# dc26_maneki-neko_badge_page01_20180626.net
KiCad netlist of a schematic drawn in EAGLE
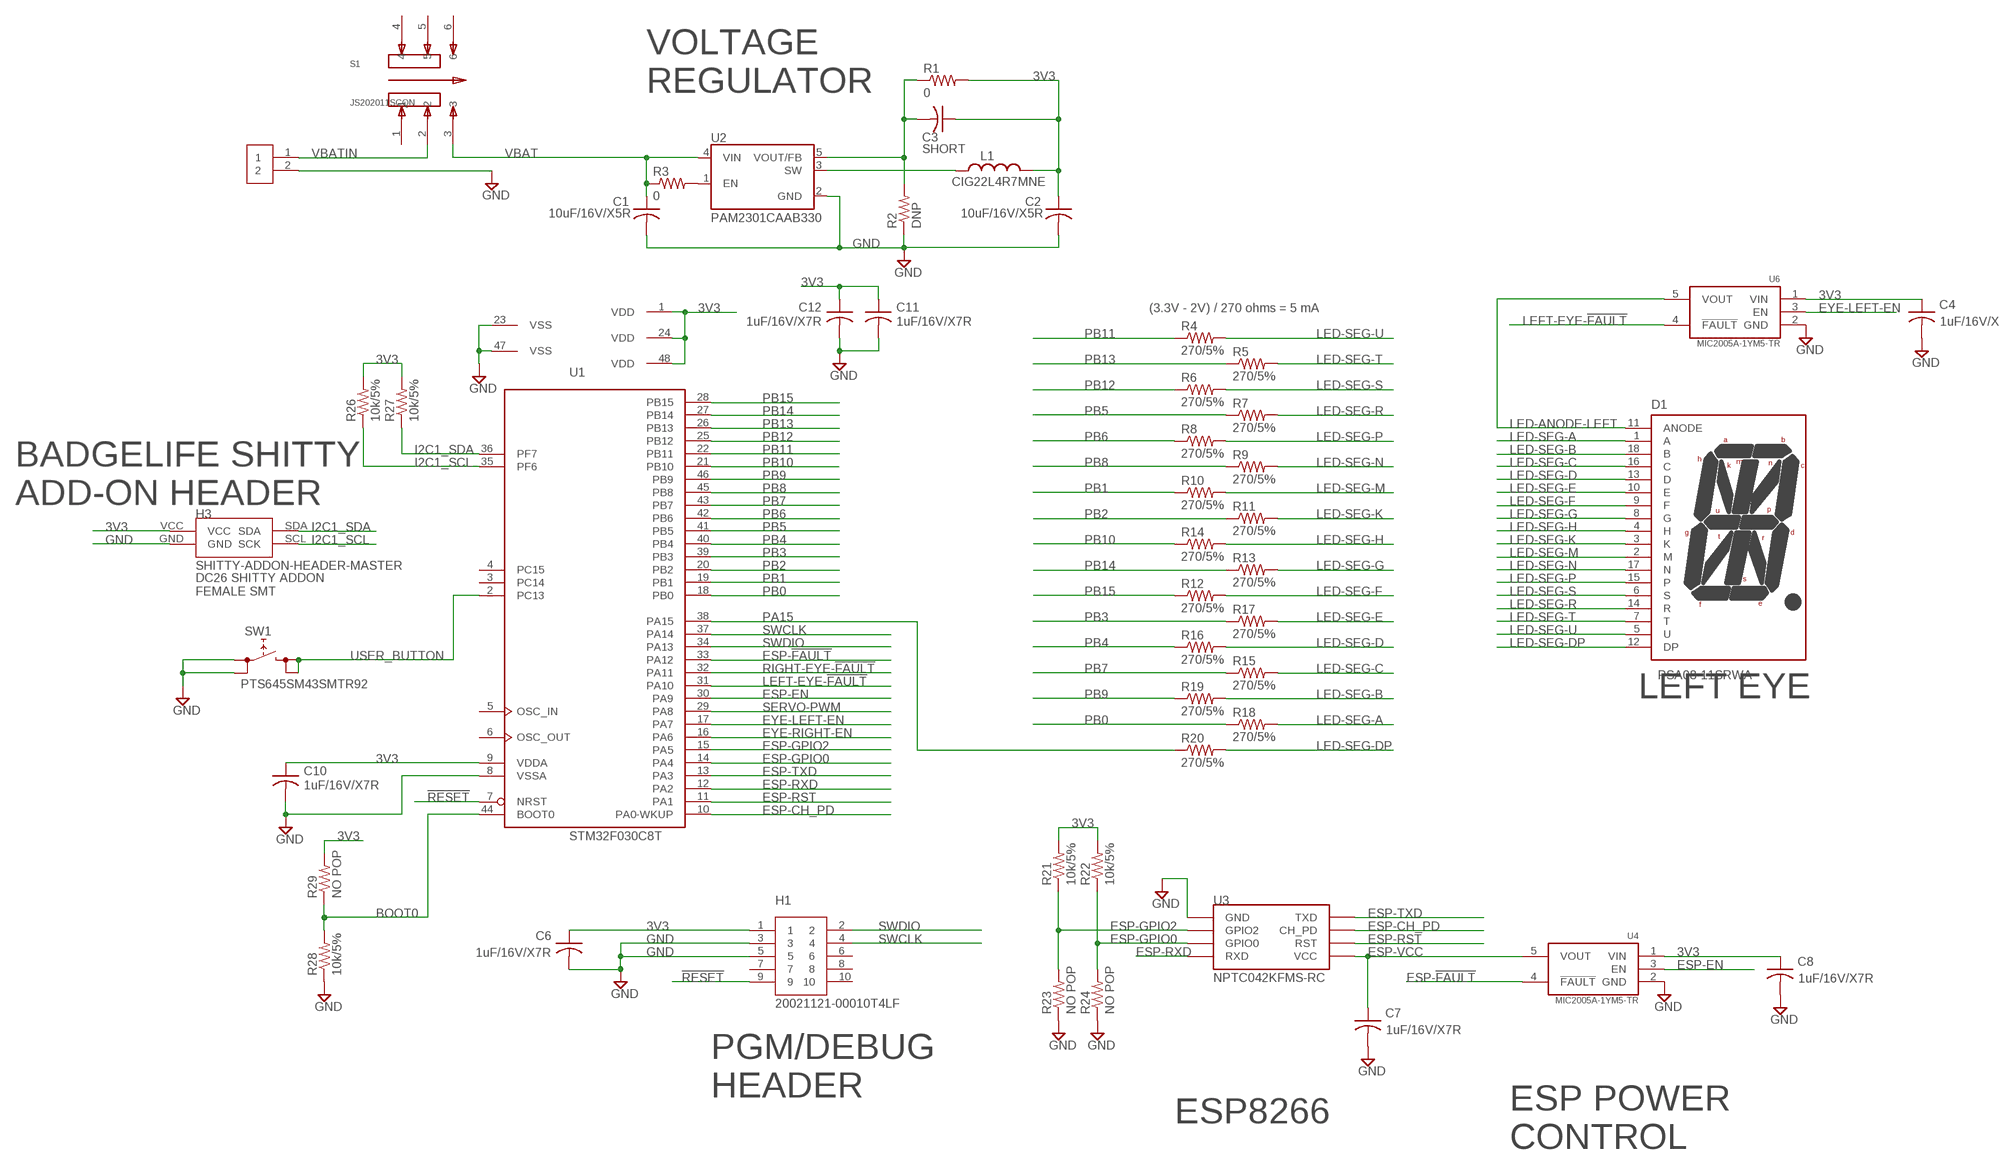
[diagram p0: schematic, sheet 1, part 1 of 2]
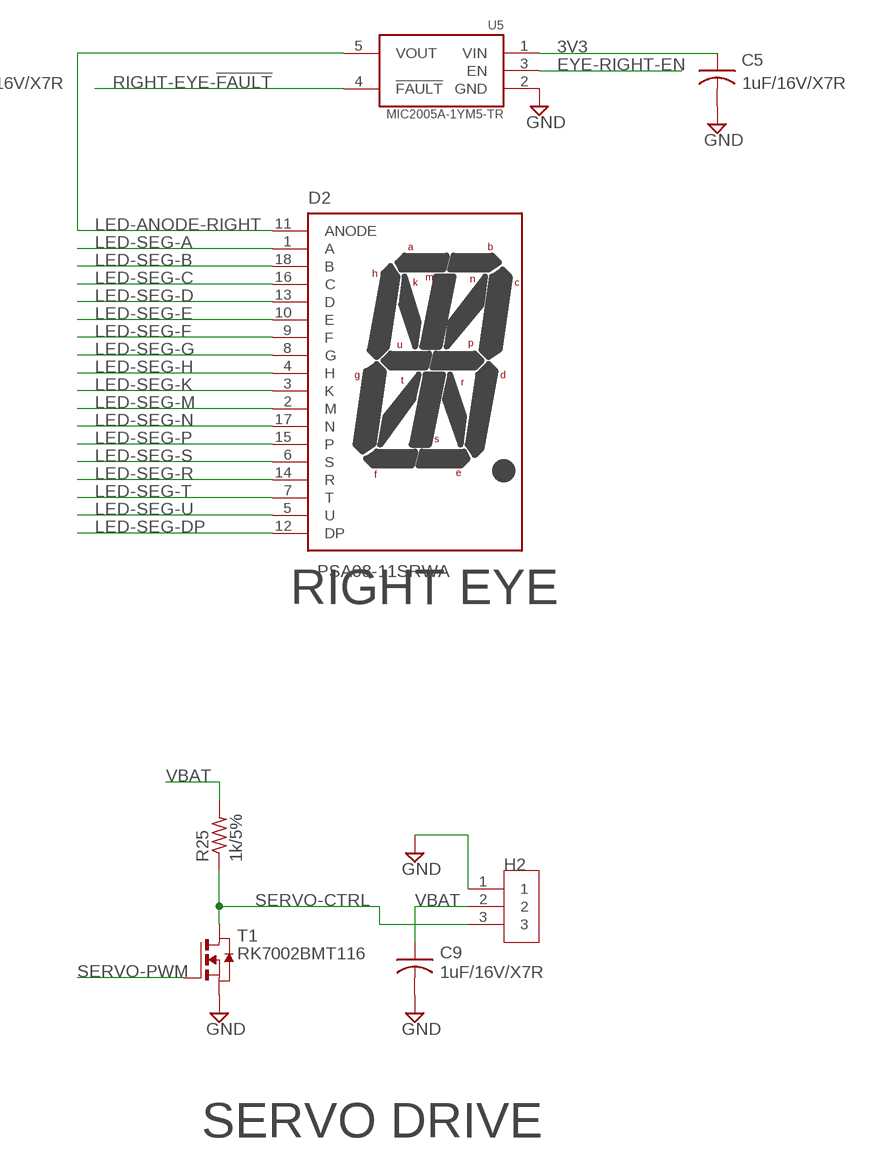
[diagram p1: schematic, sheet 1, part 2 of 2]

(export (version "E")
  (design (tool "Eeschema 10.0.6"))
  (components
    (comp (ref "C1")
      (value "10uF/16V/X5R")
      (footprint "eagle-import:C0805")
      (libsource (lib "eagle-import") (part "C-USC0805"))
    )
    (comp (ref "C2")
      (value "10uF/16V/X5R")
      (footprint "eagle-import:C0805")
      (libsource (lib "eagle-import") (part "C-USC0805"))
    )
    (comp (ref "C3")
      (value "SHORT")
      (footprint "eagle-import:C0805")
      (libsource (lib "eagle-import") (part "C-USC0805"))
    )
    (comp (ref "C4")
      (value "1uF/16V/X7R")
      (footprint "eagle-import:C0805")
      (libsource (lib "eagle-import") (part "C-USC0805"))
    )
    (comp (ref "C5")
      (value "1uF/16V/X7R")
      (footprint "eagle-import:C0805")
      (libsource (lib "eagle-import") (part "C-USC0805"))
    )
    (comp (ref "C6")
      (value "1uF/16V/X7R")
      (footprint "eagle-import:C0805")
      (libsource (lib "eagle-import") (part "C-USC0805"))
    )
    (comp (ref "C7")
      (value "1uF/16V/X7R")
      (footprint "eagle-import:C0805")
      (libsource (lib "eagle-import") (part "C-USC0805"))
    )
    (comp (ref "C8")
      (value "1uF/16V/X7R")
      (footprint "eagle-import:C0805")
      (libsource (lib "eagle-import") (part "C-USC0805"))
    )
    (comp (ref "C9")
      (value "1uF/16V/X7R")
      (footprint "eagle-import:C0805")
      (libsource (lib "eagle-import") (part "C-USC0805"))
    )
    (comp (ref "C10")
      (value "1uF/16V/X7R")
      (footprint "eagle-import:C0805")
      (libsource (lib "eagle-import") (part "C-USC0805"))
    )
    (comp (ref "C11")
      (value "1uF/16V/X7R")
      (footprint "eagle-import:C0805")
      (libsource (lib "eagle-import") (part "C-USC0805"))
    )
    (comp (ref "C12")
      (value "1uF/16V/X7R")
      (footprint "eagle-import:C0805")
      (libsource (lib "eagle-import") (part "C-USC0805"))
    )
    (comp (ref "D1")
      (value "PSA08-11SRWA")
      (footprint "eagle-import:PSA08-11SRWA")
      (libsource (lib "eagle-import") (part "PSA08-11SRWA"))
    )
    (comp (ref "D2")
      (value "PSA08-11SRWA")
      (footprint "eagle-import:PSA08-11SRWA")
      (libsource (lib "eagle-import") (part "PSA08-11SRWA"))
    )
    (comp (ref "H1")
      (value "20021121-00010T4LF")
      (footprint "eagle-import:20021121-00010T4LF")
      (libsource (lib "eagle-import") (part "20021121-00010T4LF"))
    )
    (comp (ref "H2")
      (value "M20-8890345R")
      (footprint "eagle-import:M20-8890345R")
      (libsource (lib "eagle-import") (part "M20-8890345R"))
    )
    (comp (ref "H3")
      (value "SHITTY-ADDON-HEADER-MASTER")
      (footprint "eagle-import:2X2-0.1INCH-FEMALE-SMT")
      (libsource (lib "eagle-import") (part "SHITTY-ADDON-HEADER-MASTER"))
    )
    (comp (ref "L1")
      (value "CIG22L4R7MNE")
      (footprint "eagle-import:L-1008-US")
      (libsource (lib "eagle-import") (part "CIG22L4R7MNE"))
    )
    (comp (ref "R1")
      (value "0")
      (footprint "eagle-import:R0805")
      (libsource (lib "eagle-import") (part "R-US_R0805"))
    )
    (comp (ref "R2")
      (value "DNP")
      (footprint "eagle-import:R0805")
      (libsource (lib "eagle-import") (part "R-US_R0805"))
    )
    (comp (ref "R3")
      (value "0")
      (footprint "eagle-import:R0805")
      (libsource (lib "eagle-import") (part "R-US_R0805"))
    )
    (comp (ref "R4")
      (value "270/5%")
      (footprint "eagle-import:R0805")
      (libsource (lib "eagle-import") (part "R-US_R0805"))
    )
    (comp (ref "R5")
      (value "270/5%")
      (footprint "eagle-import:R0805")
      (libsource (lib "eagle-import") (part "R-US_R0805"))
    )
    (comp (ref "R6")
      (value "270/5%")
      (footprint "eagle-import:R0805")
      (libsource (lib "eagle-import") (part "R-US_R0805"))
    )
    (comp (ref "R7")
      (value "270/5%")
      (footprint "eagle-import:R0805")
      (libsource (lib "eagle-import") (part "R-US_R0805"))
    )
    (comp (ref "R8")
      (value "270/5%")
      (footprint "eagle-import:R0805")
      (libsource (lib "eagle-import") (part "R-US_R0805"))
    )
    (comp (ref "R9")
      (value "270/5%")
      (footprint "eagle-import:R0805")
      (libsource (lib "eagle-import") (part "R-US_R0805"))
    )
    (comp (ref "R10")
      (value "270/5%")
      (footprint "eagle-import:R0805")
      (libsource (lib "eagle-import") (part "R-US_R0805"))
    )
    (comp (ref "R11")
      (value "270/5%")
      (footprint "eagle-import:R0805")
      (libsource (lib "eagle-import") (part "R-US_R0805"))
    )
    (comp (ref "R12")
      (value "270/5%")
      (footprint "eagle-import:R0805")
      (libsource (lib "eagle-import") (part "R-US_R0805"))
    )
    (comp (ref "R13")
      (value "270/5%")
      (footprint "eagle-import:R0805")
      (libsource (lib "eagle-import") (part "R-US_R0805"))
    )
    (comp (ref "R14")
      (value "270/5%")
      (footprint "eagle-import:R0805")
      (libsource (lib "eagle-import") (part "R-US_R0805"))
    )
    (comp (ref "R15")
      (value "270/5%")
      (footprint "eagle-import:R0805")
      (libsource (lib "eagle-import") (part "R-US_R0805"))
    )
    (comp (ref "R16")
      (value "270/5%")
      (footprint "eagle-import:R0805")
      (libsource (lib "eagle-import") (part "R-US_R0805"))
    )
    (comp (ref "R17")
      (value "270/5%")
      (footprint "eagle-import:R0805")
      (libsource (lib "eagle-import") (part "R-US_R0805"))
    )
    (comp (ref "R18")
      (value "270/5%")
      (footprint "eagle-import:R0805")
      (libsource (lib "eagle-import") (part "R-US_R0805"))
    )
    (comp (ref "R19")
      (value "270/5%")
      (footprint "eagle-import:R0805")
      (libsource (lib "eagle-import") (part "R-US_R0805"))
    )
    (comp (ref "R20")
      (value "270/5%")
      (footprint "eagle-import:R0805")
      (libsource (lib "eagle-import") (part "R-US_R0805"))
    )
    (comp (ref "R21")
      (value "10k/5%")
      (footprint "eagle-import:R0805")
      (libsource (lib "eagle-import") (part "R-US_R0805"))
    )
    (comp (ref "R22")
      (value "10k/5%")
      (footprint "eagle-import:R0805")
      (libsource (lib "eagle-import") (part "R-US_R0805"))
    )
    (comp (ref "R23")
      (value "NO POP")
      (footprint "eagle-import:R0805")
      (libsource (lib "eagle-import") (part "R-US_R0805"))
    )
    (comp (ref "R24")
      (value "NO POP")
      (footprint "eagle-import:R0805")
      (libsource (lib "eagle-import") (part "R-US_R0805"))
    )
    (comp (ref "R25")
      (value "1k/5%")
      (footprint "eagle-import:R0805")
      (libsource (lib "eagle-import") (part "R-US_R0805"))
    )
    (comp (ref "R26")
      (value "10k/5%")
      (footprint "eagle-import:R0805")
      (libsource (lib "eagle-import") (part "R-US_R0805"))
    )
    (comp (ref "R27")
      (value "10k/5%")
      (footprint "eagle-import:R0805")
      (libsource (lib "eagle-import") (part "R-US_R0805"))
    )
    (comp (ref "R28")
      (value "10k/5%")
      (footprint "eagle-import:R0805")
      (libsource (lib "eagle-import") (part "R-US_R0805"))
    )
    (comp (ref "R29")
      (value "NO POP")
      (footprint "eagle-import:R0805")
      (libsource (lib "eagle-import") (part "R-US_R0805"))
    )
    (comp (ref "S1")
      (value "JS202011SCQN")
      (footprint "eagle-import:SW_JS202011SCQN")
      (fields (field (name "MF") "C&K Components"))
      (libsource (lib "eagle-import") (part "JS202011SCQN"))
    )
    (comp (ref "SW1")
      (value "PTS645SM43SMTR92")
      (footprint "eagle-import:PTS645SM43SMTR92")
      (libsource (lib "eagle-import") (part "PTS645SM43SMTR92"))
    )
    (comp (ref "T1")
      (value "RK7002BMT116")
      (footprint "eagle-import:SOT-23")
      (libsource (lib "eagle-import") (part "NMOSSOT23"))
    )
    (comp (ref "U$2")
      (value "BATTPADS-SMT")
      (footprint "eagle-import:BATTPADS-SMT")
      (libsource (lib "eagle-import") (part "BATTPADS-SMT"))
    )
    (comp (ref "U1")
      (value "STM32F030C8T")
      (footprint "eagle-import:LQFP48")
      (libsource (lib "eagle-import") (part "STM32F030CT8"))
    )
    (comp (ref "U2")
      (value "PAM2301CAAB330")
      (footprint "eagle-import:SOT95P280X100-5N")
      (libsource (lib "eagle-import") (part "PAM2301CAAB330"))
    )
    (comp (ref "U3")
      (value "NPTC042KFMS-RC")
      (footprint "eagle-import:NPTC042KFMS-RC")
      (libsource (lib "eagle-import") (part "NPTC042KFMS-RC"))
    )
    (comp (ref "U4")
      (value "MIC2005A-1YM5-TR")
      (footprint "eagle-import:SOT95P270X145-5N")
      (libsource (lib "eagle-import") (part "MIC2005A-1YM5-TR"))
    )
    (comp (ref "U5")
      (value "MIC2005A-1YM5-TR")
      (footprint "eagle-import:SOT95P270X145-5N")
      (libsource (lib "eagle-import") (part "MIC2005A-1YM5-TR"))
    )
    (comp (ref "U6")
      (value "MIC2005A-1YM5-TR")
      (footprint "eagle-import:SOT95P270X145-5N")
      (libsource (lib "eagle-import") (part "MIC2005A-1YM5-TR"))
    )
  )
  (nets
    (net (code "1") (name "/3V3") (class "Default")
      (node (ref "C10") (pin "1") (pinfunction "1_1") (pintype "passive"))
      (node (ref "C11") (pin "1") (pinfunction "1_1") (pintype "passive"))
      (node (ref "C12") (pin "1") (pinfunction "1_1") (pintype "passive"))
      (node (ref "C2") (pin "1") (pinfunction "1_1") (pintype "passive"))
      (node (ref "C3") (pin "1") (pinfunction "1_1") (pintype "passive"))
      (node (ref "C4") (pin "1") (pinfunction "1_1") (pintype "passive"))
      (node (ref "C5") (pin "1") (pinfunction "1_1") (pintype "passive"))
      (node (ref "C6") (pin "1") (pinfunction "1_1") (pintype "passive"))
      (node (ref "C8") (pin "1") (pinfunction "1_1") (pintype "passive"))
      (node (ref "H1") (pin "1") (pinfunction "1_1") (pintype "bidirectional"))
      (node (ref "H3") (pin "VCC") (pinfunction "VCC_VCC") (pintype "bidirectional"))
      (node (ref "L1") (pin "P$2") (pinfunction "2_P$2") (pintype "passive"))
      (node (ref "R1") (pin "2") (pinfunction "2_2") (pintype "passive"))
      (node (ref "R21") (pin "2") (pinfunction "2_2") (pintype "passive"))
      (node (ref "R22") (pin "2") (pinfunction "2_2") (pintype "passive"))
      (node (ref "R26") (pin "2") (pinfunction "2_2") (pintype "passive"))
      (node (ref "R27") (pin "2") (pinfunction "2_2") (pintype "passive"))
      (node (ref "R29") (pin "2") (pinfunction "2_2") (pintype "passive"))
      (node (ref "U1") (pin "1") (pinfunction "VDD_1") (pintype "power_in"))
      (node (ref "U1") (pin "24") (pinfunction "VDD_24") (pintype "power_in"))
      (node (ref "U1") (pin "48") (pinfunction "VDD_48") (pintype "power_in"))
      (node (ref "U1") (pin "9") (pinfunction "VDDA_9") (pintype "power_in"))
      (node (ref "U4") (pin "1") (pinfunction "VIN_1") (pintype "bidirectional"))
      (node (ref "U5") (pin "1") (pinfunction "VIN_1") (pintype "bidirectional"))
      (node (ref "U6") (pin "1") (pinfunction "VIN_1") (pintype "bidirectional"))
    )
    (net (code "2") (name "/BOOT0") (class "Default")
      (node (ref "R28") (pin "2") (pinfunction "2_2") (pintype "passive"))
      (node (ref "R29") (pin "1") (pinfunction "1_1") (pintype "passive"))
      (node (ref "U1") (pin "44") (pinfunction "BOOT0_44") (pintype "input"))
    )
    (net (code "3") (name "/ESP-CH_PD") (class "Default")
      (node (ref "U1") (pin "10") (pinfunction "PA0-WKUP_10") (pintype "bidirectional"))
      (node (ref "U3") (pin "3") (pinfunction "CH_PD_3") (pintype "bidirectional"))
    )
    (net (code "4") (name "/ESP-EN") (class "Default")
      (node (ref "U1") (pin "30") (pinfunction "PA9_30") (pintype "bidirectional"))
      (node (ref "U4") (pin "3") (pinfunction "EN_3") (pintype "bidirectional"))
    )
    (net (code "5") (name "/ESP-GPIO0") (class "Default")
      (node (ref "R22") (pin "1") (pinfunction "1_1") (pintype "passive"))
      (node (ref "R24") (pin "2") (pinfunction "2_2") (pintype "passive"))
      (node (ref "U1") (pin "14") (pinfunction "PA4_14") (pintype "bidirectional"))
      (node (ref "U3") (pin "6") (pinfunction "GPIO0_6") (pintype "bidirectional"))
    )
    (net (code "6") (name "/ESP-GPIO2") (class "Default")
      (node (ref "R21") (pin "1") (pinfunction "1_1") (pintype "passive"))
      (node (ref "R23") (pin "2") (pinfunction "2_2") (pintype "passive"))
      (node (ref "U1") (pin "15") (pinfunction "PA5_15") (pintype "bidirectional"))
      (node (ref "U3") (pin "4") (pinfunction "GPIO2_4") (pintype "bidirectional"))
    )
    (net (code "7") (name "/ESP-RST") (class "Default")
      (node (ref "U1") (pin "11") (pinfunction "PA1_11") (pintype "bidirectional"))
      (node (ref "U3") (pin "5") (pinfunction "RST_5") (pintype "bidirectional"))
    )
    (net (code "8") (name "/ESP-RXD") (class "Default")
      (node (ref "U1") (pin "12") (pinfunction "PA2_12") (pintype "bidirectional"))
      (node (ref "U3") (pin "8") (pinfunction "RXD_8") (pintype "bidirectional"))
    )
    (net (code "9") (name "/ESP-TXD") (class "Default")
      (node (ref "U1") (pin "13") (pinfunction "PA3_13") (pintype "bidirectional"))
      (node (ref "U3") (pin "1") (pinfunction "TXD_1") (pintype "bidirectional"))
    )
    (net (code "10") (name "/ESP-VCC") (class "Default")
      (node (ref "C7") (pin "1") (pinfunction "1_1") (pintype "passive"))
      (node (ref "U3") (pin "7") (pinfunction "VCC_7") (pintype "bidirectional"))
      (node (ref "U4") (pin "5") (pinfunction "VOUT_5") (pintype "bidirectional"))
    )
    (net (code "11") (name "/ESP-~{FAULT}") (class "Default")
      (node (ref "U1") (pin "33") (pinfunction "PA12_33") (pintype "bidirectional"))
      (node (ref "U4") (pin "4") (pinfunction "~{FAULT}_4") (pintype "bidirectional"))
    )
    (net (code "12") (name "/EYE-LEFT-EN") (class "Default")
      (node (ref "U1") (pin "17") (pinfunction "PA7_17") (pintype "bidirectional"))
      (node (ref "U6") (pin "3") (pinfunction "EN_3") (pintype "bidirectional"))
    )
    (net (code "13") (name "/EYE-RIGHT-EN") (class "Default")
      (node (ref "U1") (pin "16") (pinfunction "PA6_16") (pintype "bidirectional"))
      (node (ref "U5") (pin "3") (pinfunction "EN_3") (pintype "bidirectional"))
    )
    (net (code "14") (name "/I2C1_SCL") (class "Default")
      (node (ref "H3") (pin "SCL") (pinfunction "SCK_SCL") (pintype "bidirectional"))
      (node (ref "R26") (pin "1") (pinfunction "1_1") (pintype "passive"))
      (node (ref "U1") (pin "35") (pinfunction "PF6_35") (pintype "bidirectional"))
    )
    (net (code "15") (name "/I2C1_SDA") (class "Default")
      (node (ref "H3") (pin "SDA") (pinfunction "SDA_SDA") (pintype "bidirectional"))
      (node (ref "R27") (pin "1") (pinfunction "1_1") (pintype "passive"))
      (node (ref "U1") (pin "36") (pinfunction "PF7_36") (pintype "bidirectional"))
    )
    (net (code "16") (name "/LED-ANODE-LEFT") (class "Default")
      (node (ref "D1") (pin "11") (pinfunction "ANODE_11") (pintype "bidirectional"))
      (node (ref "U6") (pin "5") (pinfunction "VOUT_5") (pintype "bidirectional"))
    )
    (net (code "17") (name "/LED-ANODE-RIGHT") (class "Default")
      (node (ref "D2") (pin "11") (pinfunction "ANODE_11") (pintype "bidirectional"))
      (node (ref "U5") (pin "5") (pinfunction "VOUT_5") (pintype "bidirectional"))
    )
    (net (code "18") (name "/LED-SEG-A") (class "Default")
      (node (ref "D1") (pin "1") (pinfunction "A_1") (pintype "bidirectional"))
      (node (ref "D2") (pin "1") (pinfunction "A_1") (pintype "bidirectional"))
      (node (ref "R18") (pin "2") (pinfunction "2_2") (pintype "passive"))
    )
    (net (code "19") (name "/LED-SEG-B") (class "Default")
      (node (ref "D1") (pin "18") (pinfunction "B_18") (pintype "bidirectional"))
      (node (ref "D2") (pin "18") (pinfunction "B_18") (pintype "bidirectional"))
      (node (ref "R19") (pin "2") (pinfunction "2_2") (pintype "passive"))
    )
    (net (code "20") (name "/LED-SEG-C") (class "Default")
      (node (ref "D1") (pin "16") (pinfunction "C_16") (pintype "bidirectional"))
      (node (ref "D2") (pin "16") (pinfunction "C_16") (pintype "bidirectional"))
      (node (ref "R15") (pin "2") (pinfunction "2_2") (pintype "passive"))
    )
    (net (code "21") (name "/LED-SEG-D") (class "Default")
      (node (ref "D1") (pin "13") (pinfunction "D_13") (pintype "bidirectional"))
      (node (ref "D2") (pin "13") (pinfunction "D_13") (pintype "bidirectional"))
      (node (ref "R16") (pin "2") (pinfunction "2_2") (pintype "passive"))
    )
    (net (code "22") (name "/LED-SEG-DP") (class "Default")
      (node (ref "D1") (pin "12") (pinfunction "DP_12") (pintype "bidirectional"))
      (node (ref "D2") (pin "12") (pinfunction "DP_12") (pintype "bidirectional"))
      (node (ref "R20") (pin "2") (pinfunction "2_2") (pintype "passive"))
    )
    (net (code "23") (name "/LED-SEG-E") (class "Default")
      (node (ref "D1") (pin "10") (pinfunction "E_10") (pintype "bidirectional"))
      (node (ref "D2") (pin "10") (pinfunction "E_10") (pintype "bidirectional"))
      (node (ref "R17") (pin "2") (pinfunction "2_2") (pintype "passive"))
    )
    (net (code "24") (name "/LED-SEG-F") (class "Default")
      (node (ref "D1") (pin "9") (pinfunction "F_9") (pintype "bidirectional"))
      (node (ref "D2") (pin "9") (pinfunction "F_9") (pintype "bidirectional"))
      (node (ref "R12") (pin "2") (pinfunction "2_2") (pintype "passive"))
    )
    (net (code "25") (name "/LED-SEG-G") (class "Default")
      (node (ref "D1") (pin "8") (pinfunction "G_8") (pintype "bidirectional"))
      (node (ref "D2") (pin "8") (pinfunction "G_8") (pintype "bidirectional"))
      (node (ref "R13") (pin "2") (pinfunction "2_2") (pintype "passive"))
    )
    (net (code "26") (name "/LED-SEG-H") (class "Default")
      (node (ref "D1") (pin "4") (pinfunction "H_4") (pintype "bidirectional"))
      (node (ref "D2") (pin "4") (pinfunction "H_4") (pintype "bidirectional"))
      (node (ref "R14") (pin "2") (pinfunction "2_2") (pintype "passive"))
    )
    (net (code "27") (name "/LED-SEG-K") (class "Default")
      (node (ref "D1") (pin "3") (pinfunction "K_3") (pintype "bidirectional"))
      (node (ref "D2") (pin "3") (pinfunction "K_3") (pintype "bidirectional"))
      (node (ref "R11") (pin "2") (pinfunction "2_2") (pintype "passive"))
    )
    (net (code "28") (name "/LED-SEG-M") (class "Default")
      (node (ref "D1") (pin "2") (pinfunction "M_2") (pintype "bidirectional"))
      (node (ref "D2") (pin "2") (pinfunction "M_2") (pintype "bidirectional"))
      (node (ref "R10") (pin "2") (pinfunction "2_2") (pintype "passive"))
    )
    (net (code "29") (name "/LED-SEG-N") (class "Default")
      (node (ref "D1") (pin "17") (pinfunction "N_17") (pintype "bidirectional"))
      (node (ref "D2") (pin "17") (pinfunction "N_17") (pintype "bidirectional"))
      (node (ref "R9") (pin "2") (pinfunction "2_2") (pintype "passive"))
    )
    (net (code "30") (name "/LED-SEG-P") (class "Default")
      (node (ref "D1") (pin "15") (pinfunction "P_15") (pintype "bidirectional"))
      (node (ref "D2") (pin "15") (pinfunction "P_15") (pintype "bidirectional"))
      (node (ref "R8") (pin "2") (pinfunction "2_2") (pintype "passive"))
    )
    (net (code "31") (name "/LED-SEG-R") (class "Default")
      (node (ref "D1") (pin "14") (pinfunction "R_14") (pintype "bidirectional"))
      (node (ref "D2") (pin "14") (pinfunction "R_14") (pintype "bidirectional"))
      (node (ref "R7") (pin "2") (pinfunction "2_2") (pintype "passive"))
    )
    (net (code "32") (name "/LED-SEG-S") (class "Default")
      (node (ref "D1") (pin "6") (pinfunction "S_6") (pintype "bidirectional"))
      (node (ref "D2") (pin "6") (pinfunction "S_6") (pintype "bidirectional"))
      (node (ref "R6") (pin "2") (pinfunction "2_2") (pintype "passive"))
    )
    (net (code "33") (name "/LED-SEG-T") (class "Default")
      (node (ref "D1") (pin "7") (pinfunction "T_7") (pintype "bidirectional"))
      (node (ref "D2") (pin "7") (pinfunction "T_7") (pintype "bidirectional"))
      (node (ref "R5") (pin "2") (pinfunction "2_2") (pintype "passive"))
    )
    (net (code "34") (name "/LED-SEG-U") (class "Default")
      (node (ref "D1") (pin "5") (pinfunction "U_5") (pintype "bidirectional"))
      (node (ref "D2") (pin "5") (pinfunction "U_5") (pintype "bidirectional"))
      (node (ref "R4") (pin "2") (pinfunction "2_2") (pintype "passive"))
    )
    (net (code "35") (name "/LEFT-EYE-~{FAULT}") (class "Default")
      (node (ref "U1") (pin "31") (pinfunction "PA10_31") (pintype "bidirectional"))
      (node (ref "U6") (pin "4") (pinfunction "~{FAULT}_4") (pintype "bidirectional"))
    )
    (net (code "36") (name "/PA15") (class "Default")
      (node (ref "R20") (pin "1") (pinfunction "1_1") (pintype "passive"))
      (node (ref "U1") (pin "38") (pinfunction "PA15_38") (pintype "bidirectional"))
    )
    (net (code "37") (name "/PB0") (class "Default")
      (node (ref "R18") (pin "1") (pinfunction "1_1") (pintype "passive"))
      (node (ref "U1") (pin "18") (pinfunction "PB0_18") (pintype "bidirectional"))
    )
    (net (code "38") (name "/PB1") (class "Default")
      (node (ref "R10") (pin "1") (pinfunction "1_1") (pintype "passive"))
      (node (ref "U1") (pin "19") (pinfunction "PB1_19") (pintype "bidirectional"))
    )
    (net (code "39") (name "/PB2") (class "Default")
      (node (ref "R11") (pin "1") (pinfunction "1_1") (pintype "passive"))
      (node (ref "U1") (pin "20") (pinfunction "PB2_20") (pintype "bidirectional"))
    )
    (net (code "40") (name "/PB3") (class "Default")
      (node (ref "R17") (pin "1") (pinfunction "1_1") (pintype "passive"))
      (node (ref "U1") (pin "39") (pinfunction "PB3_39") (pintype "bidirectional"))
    )
    (net (code "41") (name "/PB4") (class "Default")
      (node (ref "R16") (pin "1") (pinfunction "1_1") (pintype "passive"))
      (node (ref "U1") (pin "40") (pinfunction "PB4_40") (pintype "bidirectional"))
    )
    (net (code "42") (name "/PB5") (class "Default")
      (node (ref "R7") (pin "1") (pinfunction "1_1") (pintype "passive"))
      (node (ref "U1") (pin "41") (pinfunction "PB5_41") (pintype "bidirectional"))
    )
    (net (code "43") (name "/PB6") (class "Default")
      (node (ref "R8") (pin "1") (pinfunction "1_1") (pintype "passive"))
      (node (ref "U1") (pin "42") (pinfunction "PB6_42") (pintype "bidirectional"))
    )
    (net (code "44") (name "/PB7") (class "Default")
      (node (ref "R15") (pin "1") (pinfunction "1_1") (pintype "passive"))
      (node (ref "U1") (pin "43") (pinfunction "PB7_43") (pintype "bidirectional"))
    )
    (net (code "45") (name "/PB8") (class "Default")
      (node (ref "R9") (pin "1") (pinfunction "1_1") (pintype "passive"))
      (node (ref "U1") (pin "45") (pinfunction "PB8_45") (pintype "bidirectional"))
    )
    (net (code "46") (name "/PB9") (class "Default")
      (node (ref "R19") (pin "1") (pinfunction "1_1") (pintype "passive"))
      (node (ref "U1") (pin "46") (pinfunction "PB9_46") (pintype "bidirectional"))
    )
    (net (code "47") (name "/PB10") (class "Default")
      (node (ref "R14") (pin "1") (pinfunction "1_1") (pintype "passive"))
      (node (ref "U1") (pin "21") (pinfunction "PB10_21") (pintype "bidirectional"))
    )
    (net (code "48") (name "/PB11") (class "Default")
      (node (ref "R4") (pin "1") (pinfunction "1_1") (pintype "passive"))
      (node (ref "U1") (pin "22") (pinfunction "PB11_22") (pintype "bidirectional"))
    )
    (net (code "49") (name "/PB12") (class "Default")
      (node (ref "R6") (pin "1") (pinfunction "1_1") (pintype "passive"))
      (node (ref "U1") (pin "25") (pinfunction "PB12_25") (pintype "bidirectional"))
    )
    (net (code "50") (name "/PB13") (class "Default")
      (node (ref "R5") (pin "1") (pinfunction "1_1") (pintype "passive"))
      (node (ref "U1") (pin "26") (pinfunction "PB13_26") (pintype "bidirectional"))
    )
    (net (code "51") (name "/PB14") (class "Default")
      (node (ref "R13") (pin "1") (pinfunction "1_1") (pintype "passive"))
      (node (ref "U1") (pin "27") (pinfunction "PB14_27") (pintype "bidirectional"))
    )
    (net (code "52") (name "/PB15") (class "Default")
      (node (ref "R12") (pin "1") (pinfunction "1_1") (pintype "passive"))
      (node (ref "U1") (pin "28") (pinfunction "PB15_28") (pintype "bidirectional"))
    )
    (net (code "53") (name "/RIGHT-EYE-~{FAULT}") (class "Default")
      (node (ref "U1") (pin "32") (pinfunction "PA11_32") (pintype "bidirectional"))
      (node (ref "U5") (pin "4") (pinfunction "~{FAULT}_4") (pintype "bidirectional"))
    )
    (net (code "54") (name "/SERVO-CTRL") (class "Default")
      (node (ref "H2") (pin "3") (pinfunction "3_3") (pintype "bidirectional"))
      (node (ref "R25") (pin "1") (pinfunction "1_1") (pintype "passive"))
      (node (ref "T1") (pin "1") (pinfunction "D_1") (pintype "passive"))
    )
    (net (code "55") (name "/SERVO-PWM") (class "Default")
      (node (ref "T1") (pin "3") (pinfunction "G_3") (pintype "passive"))
      (node (ref "U1") (pin "29") (pinfunction "PA8_29") (pintype "bidirectional"))
    )
    (net (code "56") (name "/SWCLK") (class "Default")
      (node (ref "H1") (pin "4") (pinfunction "4_4") (pintype "bidirectional"))
      (node (ref "U1") (pin "37") (pinfunction "PA14_37") (pintype "bidirectional"))
    )
    (net (code "57") (name "/SWDIO") (class "Default")
      (node (ref "H1") (pin "2") (pinfunction "2_2") (pintype "bidirectional"))
      (node (ref "U1") (pin "34") (pinfunction "PA13_34") (pintype "bidirectional"))
    )
    (net (code "58") (name "/USER_BUTTON") (class "Default")
      (node (ref "SW1") (pin "3") (pinfunction "1_3") (pintype "passive"))
      (node (ref "SW1") (pin "4") (pinfunction "1_4") (pintype "passive"))
      (node (ref "U1") (pin "2") (pinfunction "PC13_2") (pintype "bidirectional"))
    )
    (net (code "59") (name "/VBAT") (class "Default")
      (node (ref "C1") (pin "1") (pinfunction "1_1") (pintype "passive"))
      (node (ref "C9") (pin "1") (pinfunction "1_1") (pintype "passive"))
      (node (ref "H2") (pin "2") (pinfunction "2_2") (pintype "bidirectional"))
      (node (ref "R25") (pin "2") (pinfunction "2_2") (pintype "passive"))
      (node (ref "R3") (pin "1") (pinfunction "1_1") (pintype "passive"))
      (node (ref "S1") (pin "3") (pinfunction "3_3") (pintype "passive"))
      (node (ref "U2") (pin "4") (pinfunction "VIN_4") (pintype "input"))
    )
    (net (code "60") (name "/VBATIN") (class "Default")
      (node (ref "S1") (pin "2") (pinfunction "2_2") (pintype "passive"))
      (node (ref "U$2") (pin "1") (pinfunction "1_1") (pintype "bidirectional"))
    )
    (net (code "61") (name "/~{RESET}") (class "Default")
      (node (ref "H1") (pin "9") (pinfunction "9_9") (pintype "bidirectional"))
      (node (ref "U1") (pin "7") (pinfunction "NRST_7") (pintype "bidirectional"))
    )
    (net (code "62") (name "GND") (class "Default")
      (node (ref "C1") (pin "2") (pinfunction "2_2") (pintype "passive"))
      (node (ref "C10") (pin "2") (pinfunction "2_2") (pintype "passive"))
      (node (ref "C11") (pin "2") (pinfunction "2_2") (pintype "passive"))
      (node (ref "C12") (pin "2") (pinfunction "2_2") (pintype "passive"))
      (node (ref "C2") (pin "2") (pinfunction "2_2") (pintype "passive"))
      (node (ref "C4") (pin "2") (pinfunction "2_2") (pintype "passive"))
      (node (ref "C5") (pin "2") (pinfunction "2_2") (pintype "passive"))
      (node (ref "C6") (pin "2") (pinfunction "2_2") (pintype "passive"))
      (node (ref "C7") (pin "2") (pinfunction "2_2") (pintype "passive"))
      (node (ref "C8") (pin "2") (pinfunction "2_2") (pintype "passive"))
      (node (ref "C9") (pin "2") (pinfunction "2_2") (pintype "passive"))
      (node (ref "H1") (pin "3") (pinfunction "3_3") (pintype "bidirectional"))
      (node (ref "H1") (pin "5") (pinfunction "5_5") (pintype "bidirectional"))
      (node (ref "H2") (pin "1") (pinfunction "1_1") (pintype "bidirectional"))
      (node (ref "H3") (pin "GND") (pinfunction "GND_GND") (pintype "bidirectional"))
      (node (ref "R2") (pin "1") (pinfunction "1_1") (pintype "passive"))
      (node (ref "R23") (pin "1") (pinfunction "1_1") (pintype "passive"))
      (node (ref "R24") (pin "1") (pinfunction "1_1") (pintype "passive"))
      (node (ref "R28") (pin "1") (pinfunction "1_1") (pintype "passive"))
      (node (ref "SW1") (pin "1") (pinfunction "0_1") (pintype "passive"))
      (node (ref "SW1") (pin "2") (pinfunction "0_2") (pintype "passive"))
      (node (ref "T1") (pin "2") (pinfunction "S_2") (pintype "passive"))
      (node (ref "U$2") (pin "2") (pinfunction "2_2") (pintype "bidirectional"))
      (node (ref "U1") (pin "23") (pinfunction "VSS_23") (pintype "power_in"))
      (node (ref "U1") (pin "47") (pinfunction "VSS_47") (pintype "power_in"))
      (node (ref "U1") (pin "8") (pinfunction "VSSA_8") (pintype "power_in"))
      (node (ref "U2") (pin "2") (pinfunction "GND_2") (pintype "power_in"))
      (node (ref "U3") (pin "2") (pinfunction "GND_2") (pintype "bidirectional"))
      (node (ref "U4") (pin "2") (pinfunction "GND_2") (pintype "bidirectional"))
      (node (ref "U5") (pin "2") (pinfunction "GND_2") (pintype "bidirectional"))
      (node (ref "U6") (pin "2") (pinfunction "GND_2") (pintype "bidirectional"))
    )
    (net (code "63") (name "Net-(L1-1)") (class "Default")
      (node (ref "L1") (pin "P$1") (pinfunction "1_P$1") (pintype "passive"))
      (node (ref "U2") (pin "3") (pinfunction "SW_3") (pintype "output"))
    )
    (net (code "64") (name "Net-(U2-EN)") (class "Default")
      (node (ref "R3") (pin "2") (pinfunction "2_2") (pintype "passive"))
      (node (ref "U2") (pin "1") (pinfunction "EN_1") (pintype "input"))
    )
    (net (code "65") (name "Net-(U2-VOUT{slash}FB)") (class "Default")
      (node (ref "C3") (pin "2") (pinfunction "2_2") (pintype "passive"))
      (node (ref "R1") (pin "1") (pinfunction "1_1") (pintype "passive"))
      (node (ref "R2") (pin "2") (pinfunction "2_2") (pintype "passive"))
      (node (ref "U2") (pin "5") (pinfunction "VOUT/FB_5") (pintype "output"))
    )
    (net (code "66") (name "unconnected-(H1-Pad6)") (class "Default")
      (node (ref "H1") (pin "6") (pinfunction "6_6") (pintype "bidirectional"))
    )
    (net (code "67") (name "unconnected-(H1-Pad7)") (class "Default")
      (node (ref "H1") (pin "7") (pinfunction "7_7") (pintype "bidirectional"))
    )
    (net (code "68") (name "unconnected-(H1-Pad8)") (class "Default")
      (node (ref "H1") (pin "8") (pinfunction "8_8") (pintype "bidirectional"))
    )
    (net (code "69") (name "unconnected-(H1-Pad10)") (class "Default")
      (node (ref "H1") (pin "10") (pinfunction "10_10") (pintype "bidirectional"))
    )
    (net (code "70") (name "unconnected-(S1-Pad1)") (class "Default")
      (node (ref "S1") (pin "1") (pinfunction "1_1") (pintype "passive"))
    )
    (net (code "71") (name "unconnected-(S1-Pad4)") (class "Default")
      (node (ref "S1") (pin "4") (pinfunction "4_4") (pintype "passive"))
    )
    (net (code "72") (name "unconnected-(S1-Pad5)") (class "Default")
      (node (ref "S1") (pin "5") (pinfunction "5_5") (pintype "passive"))
    )
    (net (code "73") (name "unconnected-(S1-Pad6)") (class "Default")
      (node (ref "S1") (pin "6") (pinfunction "6_6") (pintype "passive"))
    )
    (net (code "74") (name "unconnected-(U1A-OSC_IN-Pad5)") (class "Default")
      (node (ref "U1") (pin "5") (pinfunction "OSC_IN_5") (pintype "bidirectional"))
    )
    (net (code "75") (name "unconnected-(U1A-OSC_OUT-Pad6)") (class "Default")
      (node (ref "U1") (pin "6") (pinfunction "OSC_OUT_6") (pintype "bidirectional"))
    )
    (net (code "76") (name "unconnected-(U1A-PC14-Pad3)") (class "Default")
      (node (ref "U1") (pin "3") (pinfunction "PC14_3") (pintype "bidirectional"))
    )
    (net (code "77") (name "unconnected-(U1A-PC15-Pad4)") (class "Default")
      (node (ref "U1") (pin "4") (pinfunction "PC15_4") (pintype "bidirectional"))
    )
  )
)
